# SAMR21_Xplained_Pro_triple_input_power_s.net
KiCad netlist of a schematic drawn in Altium Designer
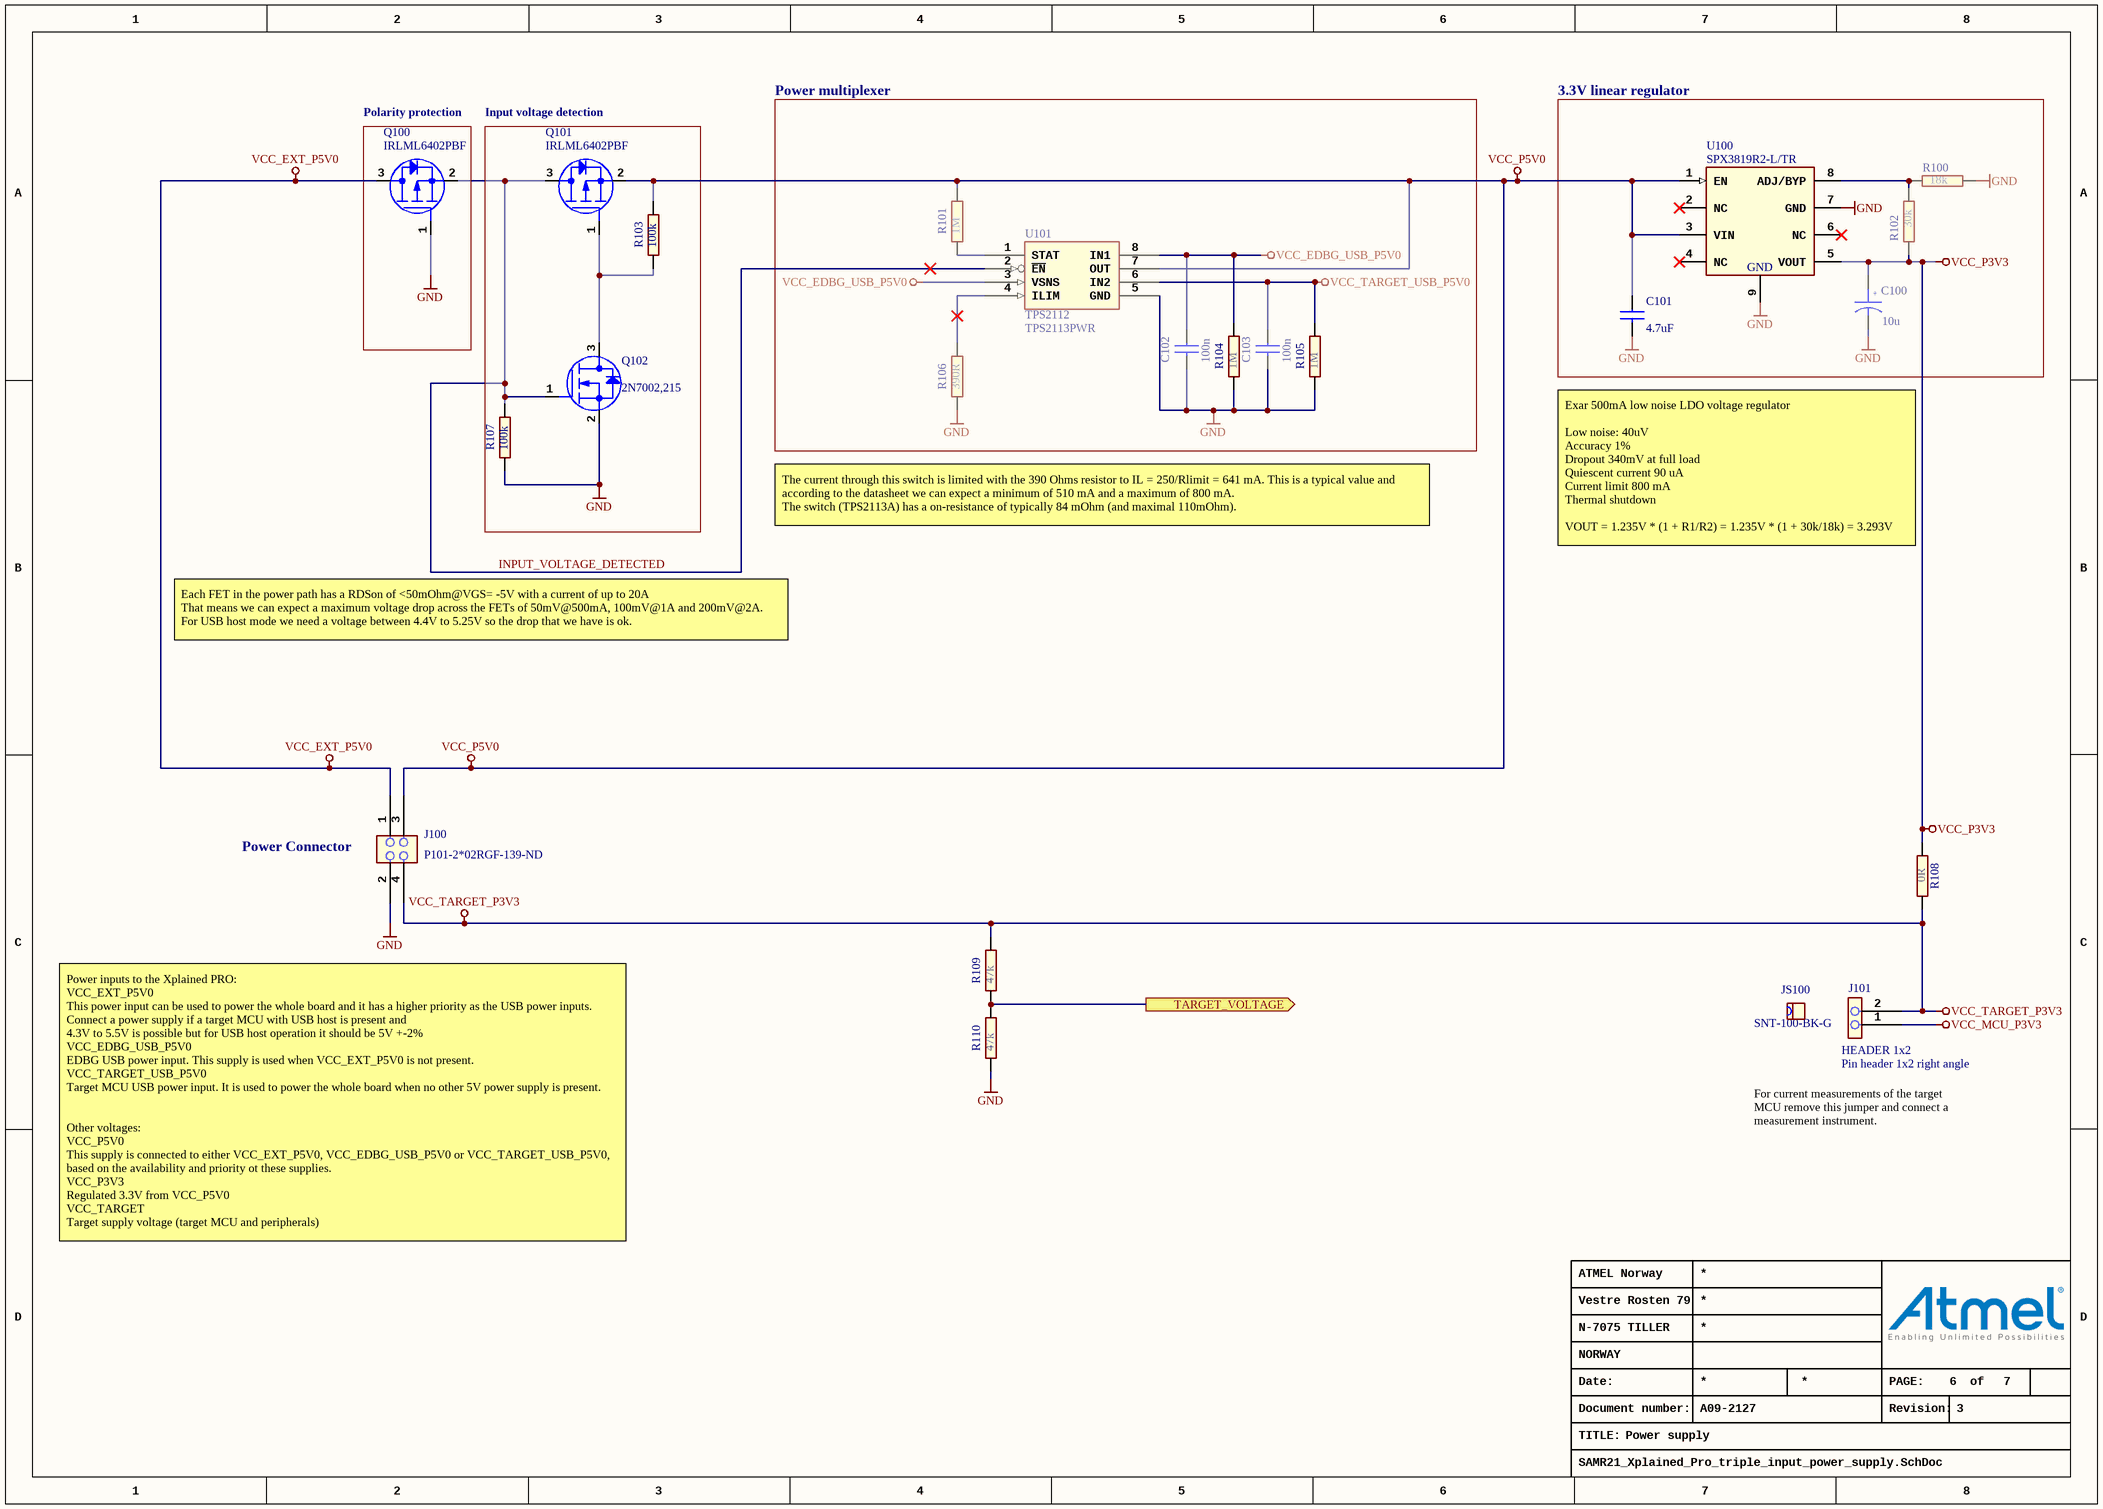
[diagram p0: SAMR21_Xplained_Pro_triple_input_power_supply.SchDoc]

(export (version "E")
  (design (tool "Eeschema 10.0.6"))
  (components
    (comp (ref "C100")
      (value "10u")
      (footprint "AP1-00036")
      (description "SMD tantalum capacitor, ESR = 1.7, 3216-18 (EIA) 1206,")
      (fields (field (name "TOLERANCE") "+-10%") (field (name "MANUFACTURER") "vishay"))
      (libsource (lib "AltiumDbLib") (part "CAP-POL"))
    )
    (comp (ref "C101")
      (value "4.7uF")
      (footprint "AP1-00039")
      (description "Ceramic capacitor, SMD 0603, X5R, 10V, 10% (de31036)")
      (fields (field (name "TOLERANCE") "10%") (field (name "MANUFACTURER") "tdk"))
      (libsource (lib "AltiumDbLib") (part "CAP-NONPOL"))
    )
    (comp (ref "C102")
      (value "100n")
      (footprint "AP1-00001")
      (description "Ceramic capacitor, SMD 0402, X7R, 16V, +/-10%")
      (fields (field (name "TOLERANCE") "16V, +/-10%") (field (name "MANUFACTURER") "Kemet"))
      (libsource (lib "AltiumDbLib") (part "CAP-NONPOL"))
    )
    (comp (ref "C103")
      (value "100n")
      (footprint "AP1-00001")
      (description "Ceramic capacitor, SMD 0402, X7R, 16V, +/-10%")
      (fields (field (name "TOLERANCE") "16V, +/-10%") (field (name "MANUFACTURER") "Kemet"))
      (libsource (lib "AltiumDbLib") (part "CAP-NONPOL"))
    )
    (comp (ref "J100")
      (value "P101-2*02RGF-139-ND")
      (footprint "AP8-00628")
      (description "Pin header, 2x2, Right Angle, 2.54mm, THT, Pin In Paste")
      (fields (field (name "Comment") "HEADER 2x2"))
      (libsource (lib "AltiumDbLib") (part "HEADER 2x2"))
    )
    (comp (ref "J101")
      (value "HEADER 1x2")
      (footprint "AP8-00367")
      (description "1x2 pin header, right angle, 2.54 mm pitch, through-hole")
      (fields
        (field (name "ALTIUM_VALUE") "Pin header 1x2 right angle")
        (field (name "MANUFACTURER") "Pro-data International Corp")
        (field (name "MPN") "2213R-2G")
      )
      (libsource (lib "AltiumDbLib") (part "HEADER 1x2"))
    )
    (comp (ref "JS100")
      (value "SNT-100-BK-G")
      (footprint "AP8-00525")
      (description "Jumper cap for 2.54mm pinheader")
      (fields (field (name "MANUFACTURER") "SAMTEC"))
      (libsource (lib "AltiumDbLib") (part "JUMPER_CAP"))
    )
    (comp (ref "Q100")
      (value "IRLML6402PBF")
      (footprint "AP5-00002")
      (description "P-ch. MOSFET. -30V, -3.7A continuous,RDS(ON)=0.05Ohm@VGS=-4,5V, RDS(ON)=0.08Ohm@VGS=-2.5V")
      (fields (field (name "MANUFACTURER") "International Rectifier") (field (name "Comment") "MOSFET_P_GSD"))
      (libsource (lib "AltiumDbLib") (part "MOSFET_P_GSD"))
    )
    (comp (ref "Q101")
      (value "IRLML6402PBF")
      (footprint "AP5-00002")
      (description "P-ch. MOSFET. -30V, -3.7A continuous,RDS(ON)=0.05Ohm@VGS=-4,5V, RDS(ON)=0.08Ohm@VGS=-2.5V")
      (fields (field (name "MANUFACTURER") "International Rectifier") (field (name "Comment") "MOSFET_P_GSD"))
      (libsource (lib "AltiumDbLib") (part "MOSFET_P_GSD"))
    )
    (comp (ref "Q102")
      (value "2N7002,215")
      (footprint "AP5-00002")
      (description "N-Channel MOSFET. 60V, 0.300A continuous, 1.2A Peak. RDS(ON) = 3.8Ohm@VGS=4.5V, VGS(th)<2.5V")
      (fields (field (name "MANUFACTURER") "NXP") (field (name "Comment") "MOSFET_N_GSD"))
      (libsource (lib "AltiumDbLib") (part "MOSFET_N_GSD"))
    )
    (comp (ref "R100")
      (value "18k")
      (footprint "AP2-00000")
      (description "Thick film resistor, SMD 0402, 1/16W, 1%")
      (fields (field (name "TOLERANCE") "1 %") (field (name "Comment") "R2"))
      (libsource (lib "") (part "R2_3"))
    )
    (comp (ref "R101")
      (value "1M")
      (footprint "AP2-00000")
      (description "Thick film resistor, SMD 0402, 1/16W, 1%")
      (fields (field (name "TOLERANCE") "1 %") (field (name "Comment") "R2"))
      (libsource (lib "") (part "R2_1"))
    )
    (comp (ref "R102")
      (value "30k")
      (footprint "AP2-00000")
      (description "Thick film resistor, SMD 0402, 1/16W, 1%")
      (fields (field (name "TOLERANCE") "1 %") (field (name "Comment") "R2"))
      (libsource (lib "") (part "R2_1"))
    )
    (comp (ref "R103")
      (value "100k")
      (footprint "AP2-00000")
      (description "Thick film resistor, SMD 0402, 1/16W, 1%")
      (fields (field (name "TOLERANCE") "1 %") (field (name "Comment") "R2"))
      (libsource (lib "") (part "R2_1"))
    )
    (comp (ref "R104")
      (value "1M")
      (footprint "AP2-00000")
      (description "Thick film resistor, SMD 0402, 1/16W, 1%")
      (fields (field (name "TOLERANCE") "1 %") (field (name "Comment") "R2"))
      (libsource (lib "") (part "R2_1"))
    )
    (comp (ref "R105")
      (value "1M")
      (footprint "AP2-00000")
      (description "Thick film resistor, SMD 0402, 1/16W, 1%")
      (fields (field (name "TOLERANCE") "1 %") (field (name "Comment") "R2"))
      (libsource (lib "") (part "R2_1"))
    )
    (comp (ref "R106")
      (value "390R")
      (footprint "AP2-00000")
      (description "Thick film resistor, SMD 0402, 1/16W, 1%")
      (fields (field (name "TOLERANCE") "1 %") (field (name "Comment") "R2"))
      (libsource (lib "") (part "R2_1"))
    )
    (comp (ref "R107")
      (value "100k")
      (footprint "AP2-00000")
      (description "Thick film resistor, SMD 0402, 1/16W, 1%")
      (fields (field (name "TOLERANCE") "1 %") (field (name "Comment") "R2"))
      (libsource (lib "") (part "R2_1"))
    )
    (comp (ref "R108")
      (value "0R")
      (footprint "AP2-00000")
      (description "Thick film resistor, SMD 0402, 1/16W, 1%")
      (fields (field (name "TOLERANCE") "1 %") (field (name "Comment") "R2"))
      (libsource (lib "") (part "R2_2"))
    )
    (comp (ref "R109")
      (value "47k")
      (footprint "AP2-00000")
      (description "Thick film resistor, SMD 0402, 1/16W, 1%")
      (fields (field (name "TOLERANCE") "1 %") (field (name "Comment") "R2"))
      (libsource (lib "AltiumDbLib") (part "R2"))
    )
    (comp (ref "R110")
      (value "47k")
      (footprint "AP2-00000")
      (description "Thick film resistor, SMD 0402, 1/16W, 1%")
      (fields (field (name "TOLERANCE") "1 %") (field (name "Comment") "R2"))
      (libsource (lib "AltiumDbLib") (part "R2"))
    )
    (comp (ref "U100")
      (value "SPX3819R2-L/TR")
      (footprint "AP6-00338")
      (description "500mA LDO, ADJ, low noise, 8-DFN package")
      (fields (field (name "TOLERANCE") "±1%") (field (name "MANUFACTURER") "Exar"))
      (libsource (lib "AltiumDbLib") (part "SPX3819R2-L"))
    )
    (comp (ref "U101")
      (value "TPS2112")
      (footprint "AP6-00054")
      (description "Autoswitching 2:1 Power Mux")
      (fields
        (field (name "ALTIUM_VALUE") "TPS2113PWR")
        (field (name "MANUFACTURER") "Texas Instruments")
        (field (name "MPN") "TPS2113PWR")
      )
      (libsource (lib "AltiumDbLib") (part "TPS2112"))
    )
  )
  (nets
    (net (code "1") (name "/INPUT_VOLTAGE_DETECTED") (class "Default")
      (node (ref "Q100") (pin "2") (pinfunction "S_2") (pintype "passive"))
      (node (ref "Q101") (pin "3") (pinfunction "D_3") (pintype "passive"))
      (node (ref "Q102") (pin "1") (pinfunction "G_1") (pintype "passive"))
      (node (ref "R107") (pin "2") (pinfunction "2_2") (pintype "passive"))
      (node (ref "U101") (pin "2") (pinfunction "~{EN}_2") (pintype "input"))
    )
    (net (code "2") (name "/TARGET_VOLTAGE") (class "Default")
      (node (ref "R109") (pin "1") (pinfunction "1_1") (pintype "passive"))
      (node (ref "R110") (pin "2") (pinfunction "2_2") (pintype "passive"))
    )
    (net (code "3") (name "GND") (class "Default")
      (node (ref "C100") (pin "2") (pinfunction "2_2") (pintype "passive"))
      (node (ref "C101") (pin "2") (pinfunction "2_2") (pintype "passive"))
      (node (ref "C102") (pin "2") (pinfunction "2_2") (pintype "passive"))
      (node (ref "C103") (pin "2") (pinfunction "2_2") (pintype "passive"))
      (node (ref "J100") (pin "2") (pinfunction "2_2") (pintype "passive"))
      (node (ref "Q100") (pin "1") (pinfunction "G_1") (pintype "passive"))
      (node (ref "Q102") (pin "2") (pinfunction "S_2") (pintype "passive"))
      (node (ref "R100") (pin "2") (pinfunction "2_2") (pintype "passive"))
      (node (ref "R104") (pin "1") (pinfunction "1_1") (pintype "passive"))
      (node (ref "R105") (pin "1") (pinfunction "1_1") (pintype "passive"))
      (node (ref "R106") (pin "1") (pinfunction "1_1") (pintype "passive"))
      (node (ref "R107") (pin "1") (pinfunction "1_1") (pintype "passive"))
      (node (ref "R110") (pin "1") (pinfunction "1_1") (pintype "passive"))
      (node (ref "U100") (pin "7") (pinfunction "GND_7") (pintype "power_in"))
      (node (ref "U100") (pin "9") (pinfunction "GND_9") (pintype "power_in"))
      (node (ref "U101") (pin "5") (pinfunction "GND_5") (pintype "power_in"))
    )
    (net (code "4") (name "Net-(Q101-G)") (class "Default")
      (node (ref "Q101") (pin "1") (pinfunction "G_1") (pintype "passive"))
      (node (ref "Q102") (pin "3") (pinfunction "D_3") (pintype "passive"))
      (node (ref "R103") (pin "1") (pinfunction "1_1") (pintype "passive"))
    )
    (net (code "5") (name "Net-(U100-ADJ{slash}BYP)") (class "Default")
      (node (ref "R100") (pin "1") (pinfunction "1_1") (pintype "passive"))
      (node (ref "R102") (pin "2") (pinfunction "2_2") (pintype "passive"))
      (node (ref "U100") (pin "8") (pinfunction "ADJ/BYP_8") (pintype "passive"))
    )
    (net (code "6") (name "Net-(U101-ILIM)") (class "Default")
      (node (ref "R106") (pin "2") (pinfunction "2_2") (pintype "passive"))
      (node (ref "U101") (pin "4") (pinfunction "ILIM_4") (pintype "input"))
    )
    (net (code "7") (name "Net-(U101-STAT)") (class "Default")
      (node (ref "R101") (pin "1") (pinfunction "1_1") (pintype "passive"))
      (node (ref "U101") (pin "1") (pinfunction "STAT_1") (pintype "open_collector"))
    )
    (net (code "8") (name "VCC_EDBG_USB_P5V0") (class "Default")
      (node (ref "C102") (pin "1") (pinfunction "1_1") (pintype "passive"))
      (node (ref "R104") (pin "2") (pinfunction "2_2") (pintype "passive"))
      (node (ref "U101") (pin "3") (pinfunction "VSNS_3") (pintype "input"))
      (node (ref "U101") (pin "8") (pinfunction "IN1_8") (pintype "power_in"))
    )
    (net (code "9") (name "VCC_EXT_P5V0") (class "Default")
      (node (ref "J100") (pin "1") (pinfunction "1_1") (pintype "passive"))
      (node (ref "Q100") (pin "3") (pinfunction "D_3") (pintype "passive"))
    )
    (net (code "10") (name "VCC_MCU_P3V3") (class "Default")
      (node (ref "J101") (pin "1") (pinfunction "1_1") (pintype "passive"))
    )
    (net (code "11") (name "VCC_P3V3") (class "Default")
      (node (ref "C100") (pin "1") (pinfunction "1_1") (pintype "passive"))
      (node (ref "R102") (pin "1") (pinfunction "1_1") (pintype "passive"))
      (node (ref "R108") (pin "1") (pinfunction "1_1") (pintype "passive"))
      (node (ref "U100") (pin "5") (pinfunction "VOUT_5") (pintype "power_in"))
    )
    (net (code "12") (name "VCC_P5V0") (class "Default")
      (node (ref "C101") (pin "1") (pinfunction "1_1") (pintype "passive"))
      (node (ref "J100") (pin "3") (pinfunction "3_3") (pintype "passive"))
      (node (ref "Q101") (pin "2") (pinfunction "S_2") (pintype "passive"))
      (node (ref "R101") (pin "2") (pinfunction "2_2") (pintype "passive"))
      (node (ref "R103") (pin "2") (pinfunction "2_2") (pintype "passive"))
      (node (ref "U100") (pin "1") (pinfunction "EN_1") (pintype "input"))
      (node (ref "U100") (pin "3") (pinfunction "VIN_3") (pintype "power_in"))
      (node (ref "U101") (pin "7") (pinfunction "OUT_7") (pintype "power_in"))
    )
    (net (code "13") (name "VCC_TARGET_P3V3") (class "Default")
      (node (ref "J100") (pin "4") (pinfunction "4_4") (pintype "passive"))
      (node (ref "J101") (pin "2") (pinfunction "2_2") (pintype "passive"))
      (node (ref "R108") (pin "2") (pinfunction "2_2") (pintype "passive"))
      (node (ref "R109") (pin "2") (pinfunction "2_2") (pintype "passive"))
    )
    (net (code "14") (name "VCC_TARGET_USB_P5V0") (class "Default")
      (node (ref "C103") (pin "1") (pinfunction "1_1") (pintype "passive"))
      (node (ref "R105") (pin "2") (pinfunction "2_2") (pintype "passive"))
      (node (ref "U101") (pin "6") (pinfunction "IN2_6") (pintype "power_in"))
    )
    (net (code "15") (name "unconnected-(U100-NC-Pad2)") (class "Default")
      (node (ref "U100") (pin "2") (pinfunction "NC_2") (pintype "passive+no_connect"))
    )
    (net (code "16") (name "unconnected-(U100-NC-Pad4)") (class "Default")
      (node (ref "U100") (pin "4") (pinfunction "NC_4") (pintype "passive+no_connect"))
    )
    (net (code "17") (name "unconnected-(U100-NC-Pad6)") (class "Default")
      (node (ref "U100") (pin "6") (pinfunction "NC_6") (pintype "passive+no_connect"))
    )
  )
)
